# SCH_ZehnderCan-V2_2024-05-12.net
KiCad netlist of a schematic drawn in EasyEDA
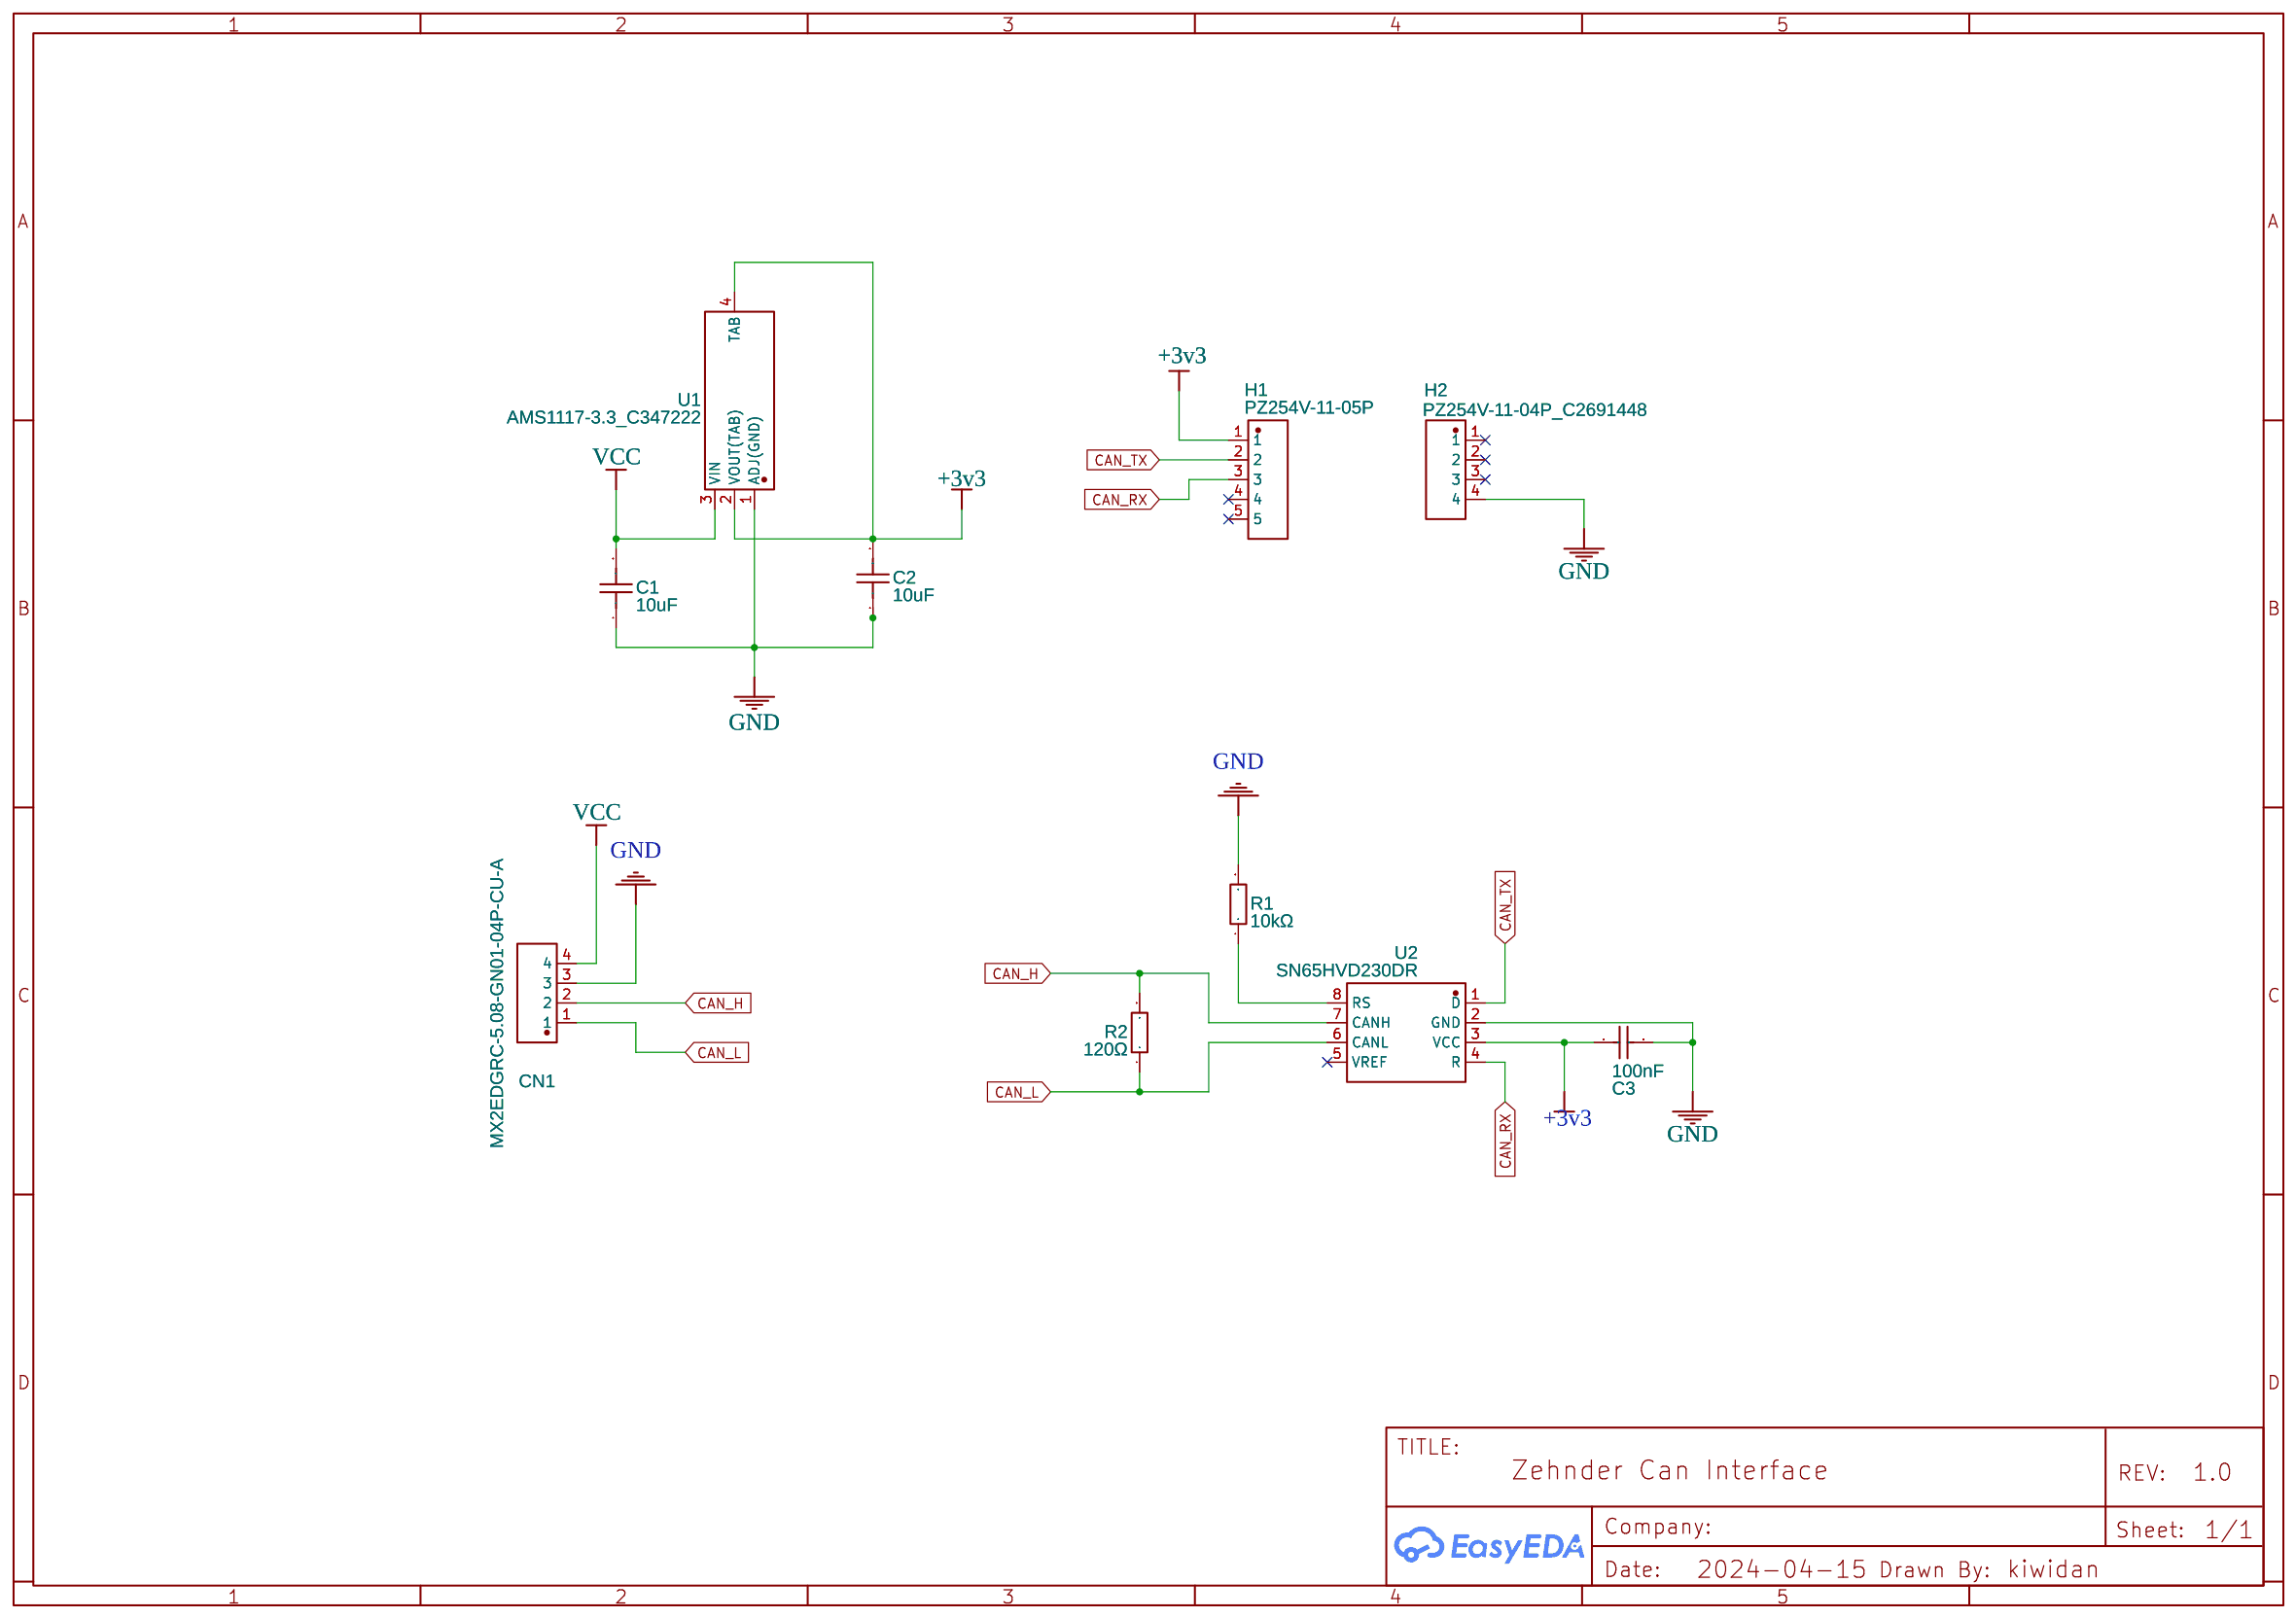
[diagram p0: schematic sheet]

(export (version "E")
  (design (tool "Eeschema 10.0.6"))
  (components
    (comp (ref "C1")
      (value "10uF")
      (fields
        (field (name "Manufacturer Part") "CL10A106MA8NRNC")
        (field (name "Manufacturer") "SAMSUNG(三星)")
      )
      (libsource (lib "") (part "CL10A106MA8NRNC"))
    )
    (comp (ref "C2")
      (value "10uF")
      (fields
        (field (name "Manufacturer Part") "CL10A106MA8NRNC")
        (field (name "Manufacturer") "SAMSUNG(三星)")
      )
      (libsource (lib "") (part "CL10A106MA8NRNC"))
    )
    (comp (ref "C3")
      (value "100nF")
      (fields
        (field (name "Manufacturer Part") "CL10B104KO8NNNC")
        (field (name "Manufacturer") "SAMSUNG(三星)")
      )
      (libsource (lib "") (part "CL10B104KO8NNNC"))
    )
    (comp (ref "CN1")
      (value "MX2EDGRC-5.08-GN01-04P-CU-A")
      (fields
        (field (name "Manufacturer Part") "MX2EDGRC-5.08-GN01-04P-Cu-A")
        (field (name "Manufacturer") "MAX(迈旭)")
      )
      (libsource (lib "") (part "MX2EDGRC-5.08-GN01-04P-CU-A"))
    )
    (comp (ref "H1")
      (value "PZ254V-11-05P")
      (fields (field (name "Manufacturer") "XFCN(兴飞)"))
      (libsource (lib "") (part "PZ254V-11-05P"))
    )
    (comp (ref "H2")
      (value "PZ254V-11-04P_C2691448")
      (fields (field (name "Manufacturer Part") "PZ254V-11-04P") (field (name "Manufacturer") "XFCN(兴飞)"))
      (libsource (lib "") (part "PZ254V-11-04P_C2691448"))
    )
    (comp (ref "R1")
      (value "10kΩ")
      (fields
        (field (name "Manufacturer Part") "0603WAF1002T5E")
        (field (name "Manufacturer") "UNI-ROYAL(厚声)")
      )
      (libsource (lib "") (part "0603WAF1002T5E"))
    )
    (comp (ref "R2")
      (value "120Ω")
      (fields
        (field (name "Manufacturer Part") "0603WAF1200T5E")
        (field (name "Manufacturer") "UNI-ROYAL(厚声)")
      )
      (libsource (lib "") (part "0603WAF1200T5E"))
    )
    (comp (ref "U1")
      (value "AMS1117-3.3_C347222")
      (fields (field (name "Manufacturer Part") "AMS1117-3.3") (field (name "Manufacturer") "UMW(友台半导体)"))
      (libsource (lib "") (part "AMS1117-3.3_C347222"))
    )
    (comp (ref "U2")
      (value "SN65HVD230DR")
      (fields (field (name "Manufacturer") "TI(德州仪器)"))
      (libsource (lib "") (part "SN65HVD230DR"))
    )
  )
  (nets
    (net (code "1") (name "+3v3") (class "Default")
      (node (ref "C2") (pin "2") (pinfunction "2_2") (pintype "unspecified"))
      (node (ref "C3") (pin "1") (pinfunction "1_1") (pintype "input"))
      (node (ref "H1") (pin "1") (pinfunction "1_1") (pintype "unspecified"))
      (node (ref "U1") (pin "2") (pinfunction "VOUT(TAB)_2") (pintype "unspecified"))
      (node (ref "U1") (pin "4") (pinfunction "TAB_4") (pintype "unspecified"))
      (node (ref "U2") (pin "3") (pinfunction "VCC_3") (pintype "unspecified"))
    )
    (net (code "2") (name "CAN_H") (class "Default")
      (node (ref "CN1") (pin "2") (pinfunction "2_2") (pintype "unspecified"))
      (node (ref "R2") (pin "2") (pinfunction "2_2") (pintype "input"))
      (node (ref "U2") (pin "7") (pinfunction "CANH_7") (pintype "unspecified"))
    )
    (net (code "3") (name "CAN_L") (class "Default")
      (node (ref "CN1") (pin "1") (pinfunction "1_1") (pintype "unspecified"))
      (node (ref "R2") (pin "1") (pinfunction "1_1") (pintype "input"))
      (node (ref "U2") (pin "6") (pinfunction "CANL_6") (pintype "unspecified"))
    )
    (net (code "4") (name "CAN_RX") (class "Default")
      (node (ref "H1") (pin "3") (pinfunction "3_3") (pintype "unspecified"))
      (node (ref "U2") (pin "4") (pinfunction "R_4") (pintype "unspecified"))
    )
    (net (code "5") (name "CAN_TX") (class "Default")
      (node (ref "H1") (pin "2") (pinfunction "2_2") (pintype "unspecified"))
      (node (ref "U2") (pin "1") (pinfunction "D_1") (pintype "unspecified"))
    )
    (net (code "6") (name "GND") (class "Default")
      (node (ref "C1") (pin "1") (pinfunction "1_1") (pintype "unspecified"))
      (node (ref "C2") (pin "1") (pinfunction "1_1") (pintype "unspecified"))
      (node (ref "C3") (pin "2") (pinfunction "2_2") (pintype "input"))
      (node (ref "CN1") (pin "3") (pinfunction "3_3") (pintype "unspecified"))
      (node (ref "H2") (pin "4") (pinfunction "4_4") (pintype "unspecified"))
      (node (ref "R1") (pin "2") (pinfunction "2_2") (pintype "input"))
      (node (ref "U1") (pin "1") (pinfunction "ADJ(GND)_1") (pintype "unspecified"))
      (node (ref "U2") (pin "2") (pinfunction "GND_2") (pintype "unspecified"))
    )
    (net (code "7") (name "Net-(U2-RS)") (class "Default")
      (node (ref "R1") (pin "1") (pinfunction "1_1") (pintype "input"))
      (node (ref "U2") (pin "8") (pinfunction "RS_8") (pintype "unspecified"))
    )
    (net (code "8") (name "VCC") (class "Default")
      (node (ref "C1") (pin "2") (pinfunction "2_2") (pintype "unspecified"))
      (node (ref "CN1") (pin "4") (pinfunction "4_4") (pintype "unspecified"))
      (node (ref "U1") (pin "3") (pinfunction "VIN_3") (pintype "unspecified"))
    )
    (net (code "9") (name "unconnected-(H1-Pad4)") (class "Default")
      (node (ref "H1") (pin "4") (pinfunction "4_4") (pintype "unspecified+no_connect"))
    )
    (net (code "10") (name "unconnected-(H1-Pad5)") (class "Default")
      (node (ref "H1") (pin "5") (pinfunction "5_5") (pintype "unspecified+no_connect"))
    )
    (net (code "11") (name "unconnected-(H2-Pad1)") (class "Default")
      (node (ref "H2") (pin "1") (pinfunction "1_1") (pintype "unspecified+no_connect"))
    )
    (net (code "12") (name "unconnected-(H2-Pad2)") (class "Default")
      (node (ref "H2") (pin "2") (pinfunction "2_2") (pintype "unspecified+no_connect"))
    )
    (net (code "13") (name "unconnected-(H2-Pad3)") (class "Default")
      (node (ref "H2") (pin "3") (pinfunction "3_3") (pintype "unspecified+no_connect"))
    )
    (net (code "14") (name "unconnected-(U2-VREF-Pad5)") (class "Default")
      (node (ref "U2") (pin "5") (pinfunction "VREF_5") (pintype "unspecified+no_connect"))
    )
  )
)
